# Hybrid_Driver.net
KiCad netlist of a schematic drawn in EAGLE
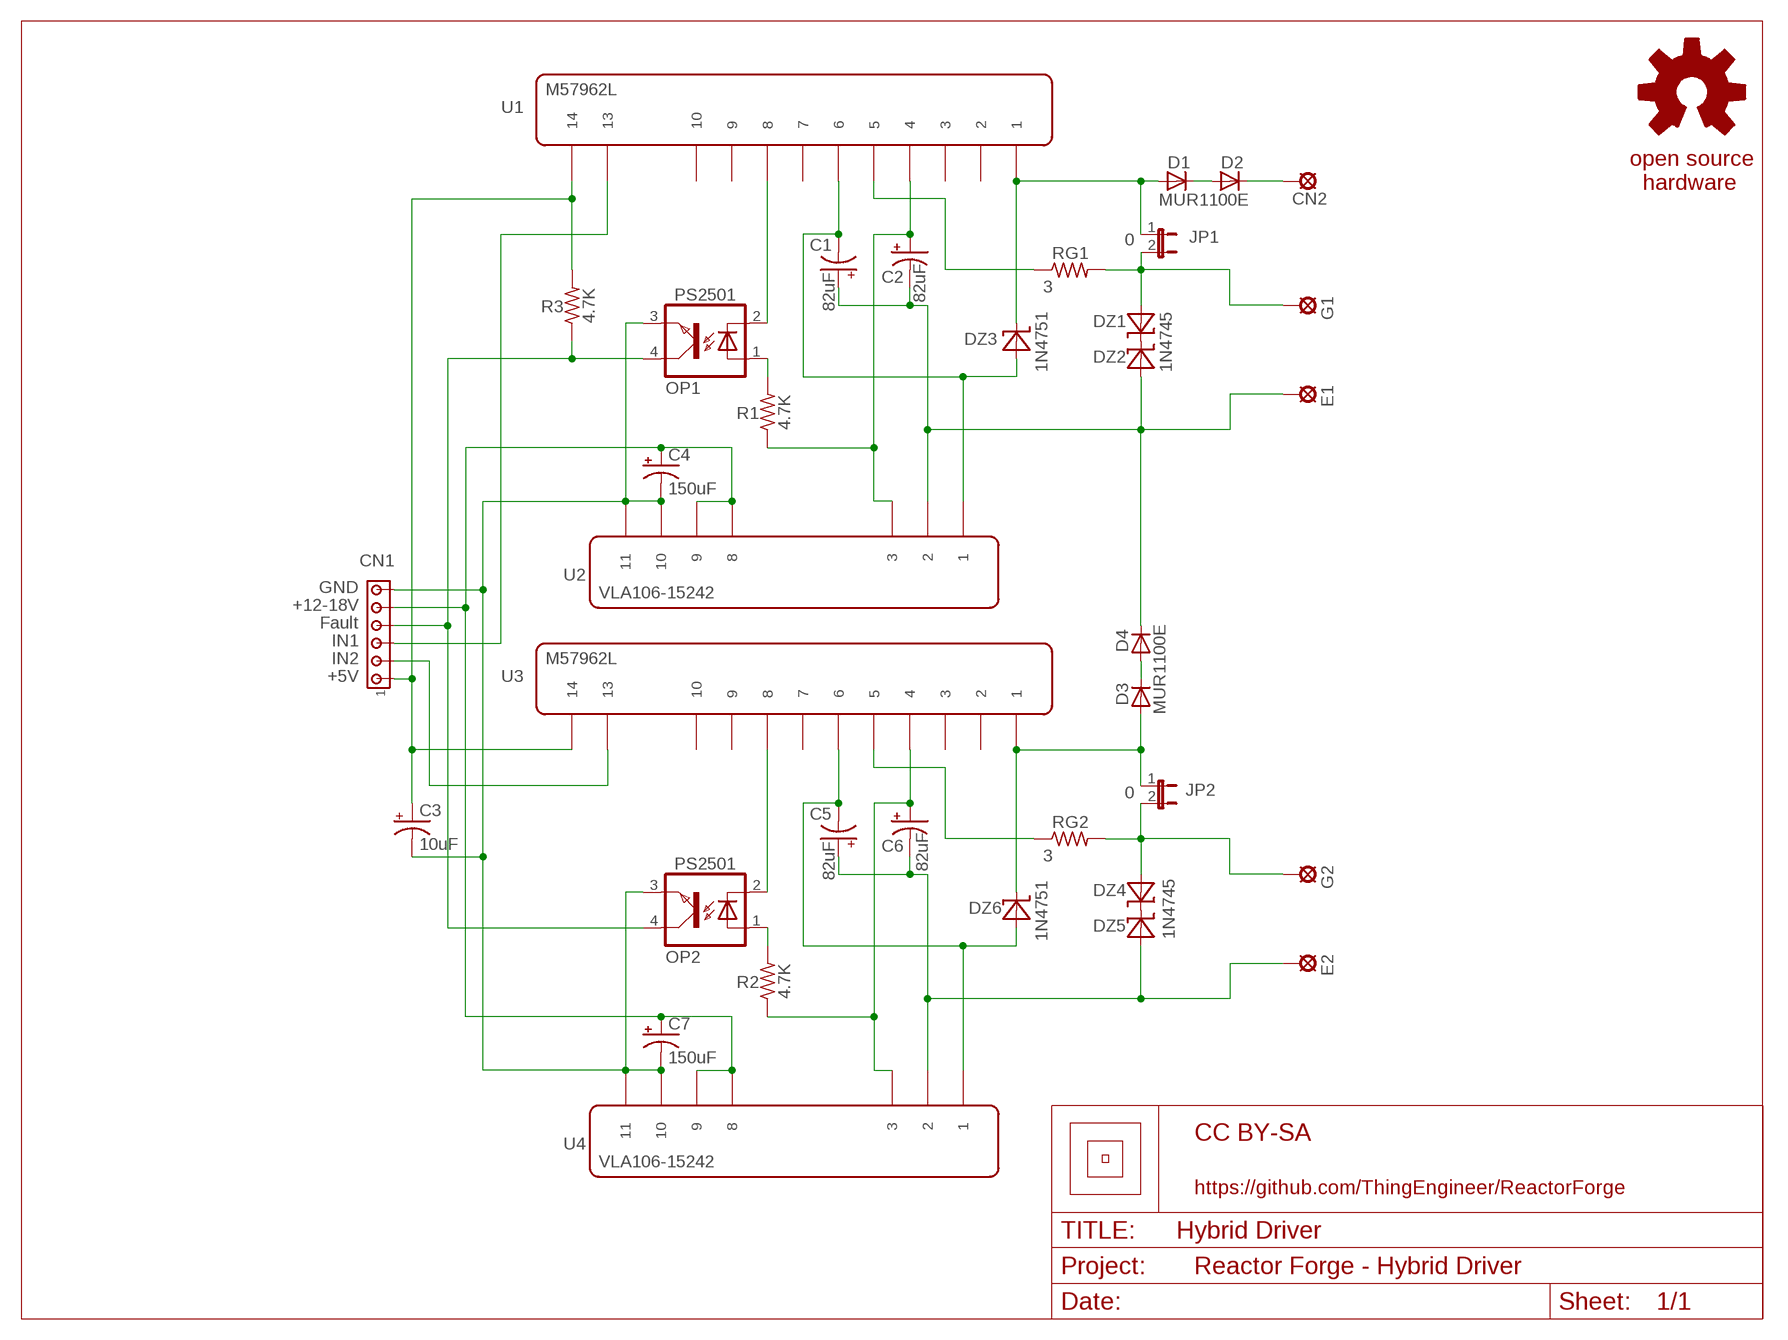
[diagram p0: schematic, sheet 1]

(export (version "E")
  (design (tool "Eeschema 10.0.6"))
  (components
    (comp (ref "C1")
      (value "82uF")
      (footprint "eagle-import:E2,5-7")
      (libsource (lib "eagle-import") (part "resistor_CPOL-USE2.5-7"))
    )
    (comp (ref "C2")
      (value "82uF")
      (footprint "eagle-import:E2,5-7")
      (libsource (lib "eagle-import") (part "resistor_CPOL-USE2.5-7"))
    )
    (comp (ref "C3")
      (value "10uF")
      (footprint "eagle-import:E2-5")
      (libsource (lib "eagle-import") (part "CPOL-USE2-5"))
    )
    (comp (ref "C4")
      (value "150uF")
      (footprint "eagle-import:E5-8,5")
      (libsource (lib "eagle-import") (part "resistor_CPOL-USE5-8.5"))
    )
    (comp (ref "C5")
      (value "82uF")
      (footprint "eagle-import:E2,5-7")
      (libsource (lib "eagle-import") (part "resistor_CPOL-USE2.5-7"))
    )
    (comp (ref "C6")
      (value "82uF")
      (footprint "eagle-import:E2,5-7")
      (libsource (lib "eagle-import") (part "resistor_CPOL-USE2.5-7"))
    )
    (comp (ref "C7")
      (value "150uF")
      (footprint "eagle-import:E5-8,5")
      (libsource (lib "eagle-import") (part "resistor_CPOL-USE5-8.5"))
    )
    (comp (ref "CN1")
      (value "MTA100-6")
      (footprint "eagle-import:10X06MTA")
      (libsource (lib "eagle-import") (part "MTA06-100"))
    )
    (comp (ref "CN2")
      (value "SE14")
      (footprint "eagle-import:SE14")
      (libsource (lib "eagle-import") (part "SE14"))
    )
    (comp (ref "D1")
      (value "MUR1100E")
      (footprint "eagle-import:DO07")
      (libsource (lib "eagle-import") (part "OA95"))
    )
    (comp (ref "D2")
      (value "MUR1100E")
      (footprint "eagle-import:DO07")
      (libsource (lib "eagle-import") (part "OA95"))
    )
    (comp (ref "D3")
      (value "MUR1100E")
      (footprint "eagle-import:DO07")
      (libsource (lib "eagle-import") (part "OA95"))
    )
    (comp (ref "D4")
      (value "MUR1100E")
      (footprint "eagle-import:DO07")
      (libsource (lib "eagle-import") (part "OA95"))
    )
    (comp (ref "DZ1")
      (value "1N4745")
      (footprint "eagle-import:DIODE.4-AXIAL")
      (libsource (lib "eagle-import") (part "1N5338"))
    )
    (comp (ref "DZ2")
      (value "1N4745")
      (footprint "eagle-import:DIODE.4-AXIAL")
      (libsource (lib "eagle-import") (part "1N5338"))
    )
    (comp (ref "DZ3")
      (value "1N4751")
      (footprint "eagle-import:DIODE.4-AXIAL")
      (libsource (lib "eagle-import") (part "1N5338"))
    )
    (comp (ref "DZ4")
      (value "1N4745")
      (footprint "eagle-import:DIODE.4-AXIAL")
      (libsource (lib "eagle-import") (part "1N5338"))
    )
    (comp (ref "DZ5")
      (value "1N4745")
      (footprint "eagle-import:DIODE.4-AXIAL")
      (libsource (lib "eagle-import") (part "1N5338"))
    )
    (comp (ref "DZ6")
      (value "1N4751")
      (footprint "eagle-import:DIODE.4-AXIAL")
      (libsource (lib "eagle-import") (part "1N5338"))
    )
    (comp (ref "E1")
      (value "IGBT-PAD")
      (footprint "eagle-import:IGBT-PAD")
      (libsource (lib "eagle-import") (part "IGBT-PAD"))
    )
    (comp (ref "E2")
      (value "IGBT-PAD")
      (footprint "eagle-import:IGBT-PAD")
      (libsource (lib "eagle-import") (part "IGBT-PAD"))
    )
    (comp (ref "G1")
      (value "IGBT-PAD")
      (footprint "eagle-import:IGBT-PAD")
      (libsource (lib "eagle-import") (part "IGBT-PAD"))
    )
    (comp (ref "G2")
      (value "IGBT-PAD")
      (footprint "eagle-import:IGBT-PAD")
      (libsource (lib "eagle-import") (part "IGBT-PAD"))
    )
    (comp (ref "GOLD_ORB_SM1")
      (value "OSHWLOGOLOGO8MM")
      (footprint "eagle-import:OSHW_8MM")
      (libsource (lib "eagle-import") (part "OSHWLOGOLOGO8MM"))
    )
    (comp (ref "JP1")
      (value "0")
      (footprint "eagle-import:JP1")
      (libsource (lib "eagle-import") (part "JP1E"))
    )
    (comp (ref "JP2")
      (value "0")
      (footprint "eagle-import:JP1")
      (libsource (lib "eagle-import") (part "JP1E"))
    )
    (comp (ref "OP1")
      (value "PS2501")
      (footprint "eagle-import:DIL04")
      (fields (field (name "MPN") "PC817X4J000F"))
      (libsource (lib "eagle-import") (part "PC817"))
    )
    (comp (ref "OP2")
      (value "PS2501")
      (footprint "eagle-import:DIL04")
      (fields (field (name "MPN") "PC817X4J000F"))
      (libsource (lib "eagle-import") (part "PC817"))
    )
    (comp (ref "R1")
      (value "4.7K")
      (footprint "eagle-import:0207_10")
      (libsource (lib "eagle-import") (part "R-US_0207/10"))
    )
    (comp (ref "R2")
      (value "4.7K")
      (footprint "eagle-import:0207_10")
      (libsource (lib "eagle-import") (part "R-US_0207/10"))
    )
    (comp (ref "R3")
      (value "4.7K")
      (footprint "eagle-import:0207_10")
      (libsource (lib "eagle-import") (part "R-US_0207/10"))
    )
    (comp (ref "RG1")
      (value "3")
      (footprint "eagle-import:0309_12")
      (libsource (lib "eagle-import") (part "R-US_0309/12"))
    )
    (comp (ref "RG2")
      (value "3")
      (footprint "eagle-import:0309_12")
      (libsource (lib "eagle-import") (part "R-US_0309/12"))
    )
    (comp (ref "U1")
      (value "M57962L")
      (footprint "eagle-import:HYBRID-IC-IBGT-GATE-DRIVER")
      (libsource (lib "eagle-import") (part "VLA504-01"))
    )
    (comp (ref "U2")
      (value "VLA106-15242")
      (footprint "eagle-import:ISOLATED_DC_DC_CONVERTER")
      (libsource (lib "eagle-import") (part "VLA106-15242"))
    )
    (comp (ref "U3")
      (value "M57962L")
      (footprint "eagle-import:HYBRID-IC-IBGT-GATE-DRIVER")
      (libsource (lib "eagle-import") (part "VLA504-01"))
    )
    (comp (ref "U4")
      (value "VLA106-15242")
      (footprint "eagle-import:ISOLATED_DC_DC_CONVERTER")
      (libsource (lib "eagle-import") (part "VLA106-15242"))
    )
  )
  (nets
    (net (code "1") (name "Net-(C1-Pad+)") (class "Default")
      (node (ref "C1") (pin "+") (pinfunction "+_+") (pintype "passive"))
      (node (ref "C2") (pin "-") (pinfunction "-_-") (pintype "passive"))
      (node (ref "D4") (pin "C") (pinfunction "C_C") (pintype "passive"))
      (node (ref "DZ2") (pin "A") (pinfunction "A_A") (pintype "passive"))
      (node (ref "E1") (pin "1") (pinfunction "1_1") (pintype "passive"))
      (node (ref "E1") (pin "2") (pinfunction "1_2") (pintype "passive"))
      (node (ref "E1") (pin "3") (pinfunction "1_3") (pintype "passive"))
      (node (ref "E1") (pin "4") (pinfunction "1_4") (pintype "passive"))
      (node (ref "E1") (pin "5") (pinfunction "1_5") (pintype "passive"))
      (node (ref "E1") (pin "6") (pinfunction "1_6") (pintype "passive"))
      (node (ref "U2") (pin "2") (pinfunction "2_2") (pintype "bidirectional"))
    )
    (net (code "2") (name "Net-(C1-Pad-)") (class "Default")
      (node (ref "C1") (pin "-") (pinfunction "-_-") (pintype "passive"))
      (node (ref "DZ3") (pin "A") (pinfunction "A_A") (pintype "passive"))
      (node (ref "U1") (pin "6") (pinfunction "6_6") (pintype "bidirectional"))
      (node (ref "U2") (pin "1") (pinfunction "1_1") (pintype "bidirectional"))
    )
    (net (code "3") (name "Net-(C2-Pad+)") (class "Default")
      (node (ref "C2") (pin "+") (pinfunction "+_+") (pintype "passive"))
      (node (ref "R1") (pin "1") (pinfunction "1_1") (pintype "passive"))
      (node (ref "U1") (pin "4") (pinfunction "4_4") (pintype "bidirectional"))
      (node (ref "U2") (pin "3") (pinfunction "3_3") (pintype "bidirectional"))
    )
    (net (code "4") (name "Net-(C5-Pad+)") (class "Default")
      (node (ref "C5") (pin "+") (pinfunction "+_+") (pintype "passive"))
      (node (ref "C6") (pin "-") (pinfunction "-_-") (pintype "passive"))
      (node (ref "DZ5") (pin "A") (pinfunction "A_A") (pintype "passive"))
      (node (ref "E2") (pin "1") (pinfunction "1_1") (pintype "passive"))
      (node (ref "E2") (pin "2") (pinfunction "1_2") (pintype "passive"))
      (node (ref "E2") (pin "3") (pinfunction "1_3") (pintype "passive"))
      (node (ref "E2") (pin "4") (pinfunction "1_4") (pintype "passive"))
      (node (ref "E2") (pin "5") (pinfunction "1_5") (pintype "passive"))
      (node (ref "E2") (pin "6") (pinfunction "1_6") (pintype "passive"))
      (node (ref "U4") (pin "2") (pinfunction "2_2") (pintype "bidirectional"))
    )
    (net (code "5") (name "Net-(C5-Pad-)") (class "Default")
      (node (ref "C5") (pin "-") (pinfunction "-_-") (pintype "passive"))
      (node (ref "DZ6") (pin "A") (pinfunction "A_A") (pintype "passive"))
      (node (ref "U3") (pin "6") (pinfunction "6_6") (pintype "bidirectional"))
      (node (ref "U4") (pin "1") (pinfunction "1_1") (pintype "bidirectional"))
    )
    (net (code "6") (name "Net-(C6-Pad+)") (class "Default")
      (node (ref "C6") (pin "+") (pinfunction "+_+") (pintype "passive"))
      (node (ref "R2") (pin "1") (pinfunction "1_1") (pintype "passive"))
      (node (ref "U3") (pin "4") (pinfunction "4_4") (pintype "bidirectional"))
      (node (ref "U4") (pin "3") (pinfunction "3_3") (pintype "bidirectional"))
    )
    (net (code "7") (name "Net-(CN1-1)") (class "Default")
      (node (ref "C3") (pin "+") (pinfunction "+_+") (pintype "passive"))
      (node (ref "CN1") (pin "6") (pinfunction "1_6") (pintype "passive"))
      (node (ref "R3") (pin "2") (pinfunction "2_2") (pintype "passive"))
      (node (ref "U1") (pin "14") (pinfunction "14_14") (pintype "bidirectional"))
      (node (ref "U3") (pin "14") (pinfunction "14_14") (pintype "bidirectional"))
    )
    (net (code "8") (name "Net-(CN1-2)") (class "Default")
      (node (ref "CN1") (pin "5") (pinfunction "2_5") (pintype "passive"))
      (node (ref "U3") (pin "13") (pinfunction "13_13") (pintype "bidirectional"))
    )
    (net (code "9") (name "Net-(CN1-3)") (class "Default")
      (node (ref "CN1") (pin "4") (pinfunction "3_4") (pintype "passive"))
      (node (ref "U1") (pin "13") (pinfunction "13_13") (pintype "bidirectional"))
    )
    (net (code "10") (name "Net-(CN1-4)") (class "Default")
      (node (ref "CN1") (pin "3") (pinfunction "4_3") (pintype "passive"))
      (node (ref "OP1") (pin "4") (pinfunction "COL_4") (pintype "passive"))
      (node (ref "OP2") (pin "4") (pinfunction "COL_4") (pintype "passive"))
      (node (ref "R3") (pin "1") (pinfunction "1_1") (pintype "passive"))
    )
    (net (code "11") (name "Net-(CN1-5)") (class "Default")
      (node (ref "C4") (pin "+") (pinfunction "+_+") (pintype "passive"))
      (node (ref "C7") (pin "+") (pinfunction "+_+") (pintype "passive"))
      (node (ref "CN1") (pin "2") (pinfunction "5_2") (pintype "passive"))
      (node (ref "U2") (pin "8") (pinfunction "8_8") (pintype "bidirectional"))
      (node (ref "U2") (pin "9") (pinfunction "9_9") (pintype "bidirectional"))
      (node (ref "U4") (pin "8") (pinfunction "8_8") (pintype "bidirectional"))
      (node (ref "U4") (pin "9") (pinfunction "9_9") (pintype "bidirectional"))
    )
    (net (code "12") (name "Net-(CN1-6)") (class "Default")
      (node (ref "C3") (pin "-") (pinfunction "-_-") (pintype "passive"))
      (node (ref "C4") (pin "-") (pinfunction "-_-") (pintype "passive"))
      (node (ref "C7") (pin "-") (pinfunction "-_-") (pintype "passive"))
      (node (ref "CN1") (pin "1") (pinfunction "6_1") (pintype "passive"))
      (node (ref "OP1") (pin "3") (pinfunction "EMIT_3") (pintype "passive"))
      (node (ref "OP2") (pin "3") (pinfunction "EMIT_3") (pintype "passive"))
      (node (ref "U2") (pin "10") (pinfunction "10_10") (pintype "bidirectional"))
      (node (ref "U2") (pin "11") (pinfunction "11_11") (pintype "bidirectional"))
      (node (ref "U4") (pin "10") (pinfunction "10_10") (pintype "bidirectional"))
      (node (ref "U4") (pin "11") (pinfunction "11_11") (pintype "bidirectional"))
    )
    (net (code "13") (name "Net-(CN2-PadMP)") (class "Default")
      (node (ref "CN2") (pin "MP") (pinfunction "MP_MP") (pintype "passive"))
      (node (ref "D2") (pin "C") (pinfunction "C_C") (pintype "passive"))
    )
    (net (code "14") (name "Net-(D1-PadA)") (class "Default")
      (node (ref "D1") (pin "A") (pinfunction "A_A") (pintype "passive"))
      (node (ref "DZ3") (pin "C") (pinfunction "C_C") (pintype "passive"))
      (node (ref "JP1") (pin "1") (pinfunction "1_1") (pintype "passive"))
      (node (ref "U1") (pin "1") (pinfunction "1_1") (pintype "bidirectional"))
    )
    (net (code "15") (name "Net-(D1-PadC)") (class "Default")
      (node (ref "D1") (pin "C") (pinfunction "C_C") (pintype "passive"))
      (node (ref "D2") (pin "A") (pinfunction "A_A") (pintype "passive"))
    )
    (net (code "16") (name "Net-(D3-PadA)") (class "Default")
      (node (ref "D3") (pin "A") (pinfunction "A_A") (pintype "passive"))
      (node (ref "DZ6") (pin "C") (pinfunction "C_C") (pintype "passive"))
      (node (ref "JP2") (pin "1") (pinfunction "1_1") (pintype "passive"))
      (node (ref "U3") (pin "1") (pinfunction "1_1") (pintype "bidirectional"))
    )
    (net (code "17") (name "Net-(D3-PadC)") (class "Default")
      (node (ref "D3") (pin "C") (pinfunction "C_C") (pintype "passive"))
      (node (ref "D4") (pin "A") (pinfunction "A_A") (pintype "passive"))
    )
    (net (code "18") (name "Net-(DZ1-PadA)") (class "Default")
      (node (ref "DZ1") (pin "A") (pinfunction "A_A") (pintype "passive"))
      (node (ref "G1") (pin "1") (pinfunction "1_1") (pintype "passive"))
      (node (ref "G1") (pin "2") (pinfunction "1_2") (pintype "passive"))
      (node (ref "G1") (pin "3") (pinfunction "1_3") (pintype "passive"))
      (node (ref "G1") (pin "4") (pinfunction "1_4") (pintype "passive"))
      (node (ref "G1") (pin "5") (pinfunction "1_5") (pintype "passive"))
      (node (ref "G1") (pin "6") (pinfunction "1_6") (pintype "passive"))
      (node (ref "JP1") (pin "2") (pinfunction "2_2") (pintype "passive"))
      (node (ref "RG1") (pin "2") (pinfunction "2_2") (pintype "passive"))
    )
    (net (code "19") (name "Net-(DZ1-PadC)") (class "Default")
      (node (ref "DZ1") (pin "C") (pinfunction "C_C") (pintype "passive"))
      (node (ref "DZ2") (pin "C") (pinfunction "C_C") (pintype "passive"))
    )
    (net (code "20") (name "Net-(DZ4-PadA)") (class "Default")
      (node (ref "DZ4") (pin "A") (pinfunction "A_A") (pintype "passive"))
      (node (ref "G2") (pin "1") (pinfunction "1_1") (pintype "passive"))
      (node (ref "G2") (pin "2") (pinfunction "1_2") (pintype "passive"))
      (node (ref "G2") (pin "3") (pinfunction "1_3") (pintype "passive"))
      (node (ref "G2") (pin "4") (pinfunction "1_4") (pintype "passive"))
      (node (ref "G2") (pin "5") (pinfunction "1_5") (pintype "passive"))
      (node (ref "G2") (pin "6") (pinfunction "1_6") (pintype "passive"))
      (node (ref "JP2") (pin "2") (pinfunction "2_2") (pintype "passive"))
      (node (ref "RG2") (pin "2") (pinfunction "2_2") (pintype "passive"))
    )
    (net (code "21") (name "Net-(DZ4-PadC)") (class "Default")
      (node (ref "DZ4") (pin "C") (pinfunction "C_C") (pintype "passive"))
      (node (ref "DZ5") (pin "C") (pinfunction "C_C") (pintype "passive"))
    )
    (net (code "22") (name "Net-(OP1-A)") (class "Default")
      (node (ref "OP1") (pin "1") (pinfunction "A_1") (pintype "passive"))
      (node (ref "R1") (pin "2") (pinfunction "2_2") (pintype "passive"))
    )
    (net (code "23") (name "Net-(OP1-C)") (class "Default")
      (node (ref "OP1") (pin "2") (pinfunction "C_2") (pintype "passive"))
      (node (ref "U1") (pin "8") (pinfunction "8_8") (pintype "bidirectional"))
    )
    (net (code "24") (name "Net-(OP2-A)") (class "Default")
      (node (ref "OP2") (pin "1") (pinfunction "A_1") (pintype "passive"))
      (node (ref "R2") (pin "2") (pinfunction "2_2") (pintype "passive"))
    )
    (net (code "25") (name "Net-(OP2-C)") (class "Default")
      (node (ref "OP2") (pin "2") (pinfunction "C_2") (pintype "passive"))
      (node (ref "U3") (pin "8") (pinfunction "8_8") (pintype "bidirectional"))
    )
    (net (code "26") (name "Net-(RG1-Pad1)") (class "Default")
      (node (ref "RG1") (pin "1") (pinfunction "1_1") (pintype "passive"))
      (node (ref "U1") (pin "5") (pinfunction "5_5") (pintype "bidirectional"))
    )
    (net (code "27") (name "Net-(RG2-Pad1)") (class "Default")
      (node (ref "RG2") (pin "1") (pinfunction "1_1") (pintype "passive"))
      (node (ref "U3") (pin "5") (pinfunction "5_5") (pintype "bidirectional"))
    )
    (net (code "28") (name "unconnected-(U1-Pad2)") (class "Default")
      (node (ref "U1") (pin "2") (pinfunction "2_2") (pintype "bidirectional"))
    )
    (net (code "29") (name "unconnected-(U1-Pad3)") (class "Default")
      (node (ref "U1") (pin "3") (pinfunction "3_3") (pintype "bidirectional"))
    )
    (net (code "30") (name "unconnected-(U1-Pad7)") (class "Default")
      (node (ref "U1") (pin "7") (pinfunction "7_7") (pintype "bidirectional"))
    )
    (net (code "31") (name "unconnected-(U1-Pad9)") (class "Default")
      (node (ref "U1") (pin "9") (pinfunction "9_9") (pintype "bidirectional"))
    )
    (net (code "32") (name "unconnected-(U1-Pad10)") (class "Default")
      (node (ref "U1") (pin "10") (pinfunction "10_10") (pintype "bidirectional"))
    )
    (net (code "33") (name "unconnected-(U3-Pad2)") (class "Default")
      (node (ref "U3") (pin "2") (pinfunction "2_2") (pintype "bidirectional"))
    )
    (net (code "34") (name "unconnected-(U3-Pad3)") (class "Default")
      (node (ref "U3") (pin "3") (pinfunction "3_3") (pintype "bidirectional"))
    )
    (net (code "35") (name "unconnected-(U3-Pad7)") (class "Default")
      (node (ref "U3") (pin "7") (pinfunction "7_7") (pintype "bidirectional"))
    )
    (net (code "36") (name "unconnected-(U3-Pad9)") (class "Default")
      (node (ref "U3") (pin "9") (pinfunction "9_9") (pintype "bidirectional"))
    )
    (net (code "37") (name "unconnected-(U3-Pad10)") (class "Default")
      (node (ref "U3") (pin "10") (pinfunction "10_10") (pintype "bidirectional"))
    )
  )
)
